# learn_to_solder.net
KiCad netlist of a schematic drawn in EAGLE
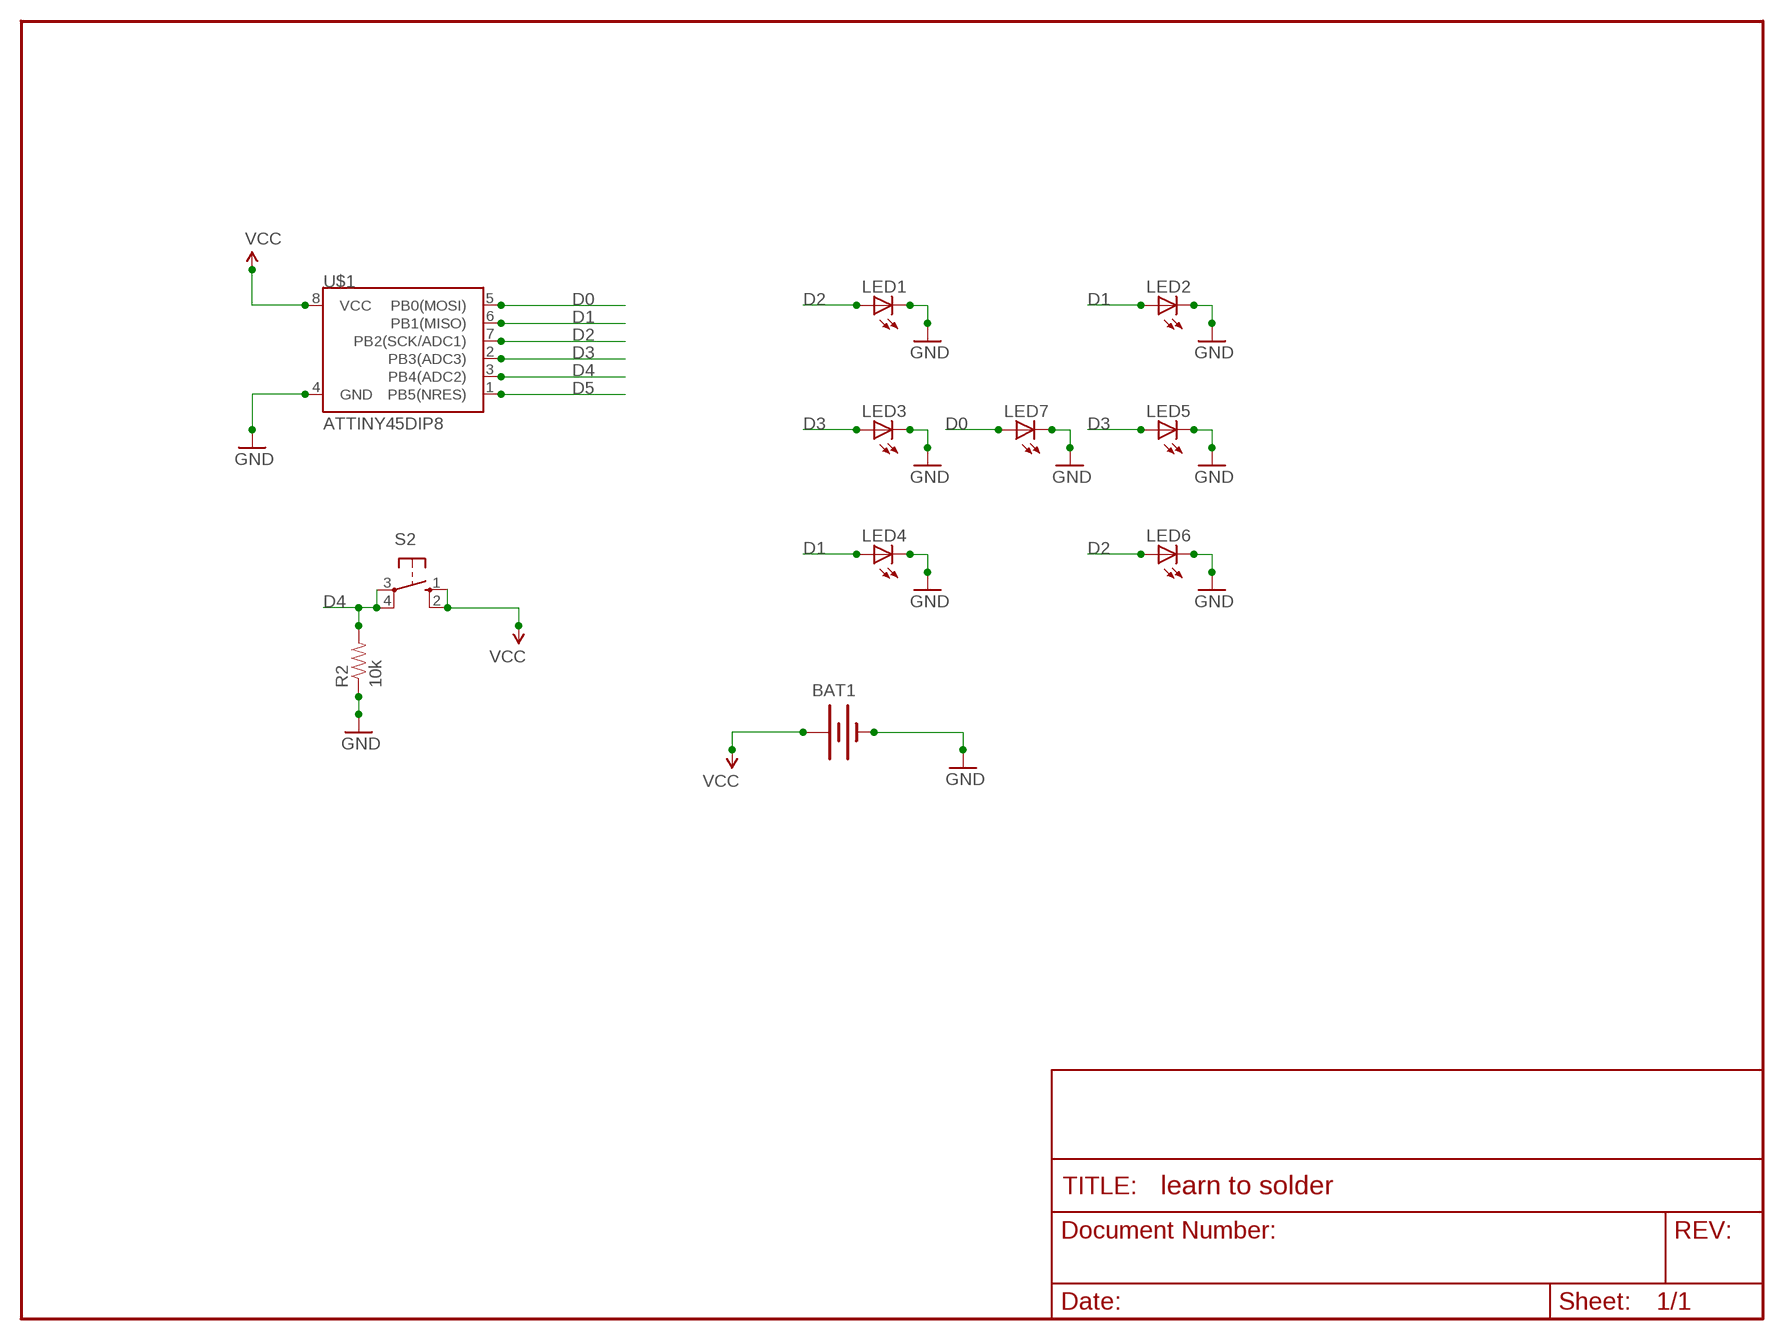
[diagram p0: schematic, sheet 1]

(export (version "E")
  (design (tool "Eeschema 10.0.6"))
  (components
    (comp (ref "BAT1")
      (value "BATTERY20PTH")
      (footprint "eagle-import:BATTCOM_20MM_PTH")
      (libsource (lib "eagle-import") (part "BATTERY20PTH"))
    )
    (comp (ref "LED1")
      (value "LED5MM")
      (footprint "eagle-import:LED5MM")
      (libsource (lib "eagle-import") (part "LED5MM"))
    )
    (comp (ref "LED2")
      (value "LED5MM")
      (footprint "eagle-import:LED5MM")
      (libsource (lib "eagle-import") (part "LED5MM"))
    )
    (comp (ref "LED3")
      (value "LED5MM")
      (footprint "eagle-import:LED5MM")
      (libsource (lib "eagle-import") (part "LED5MM"))
    )
    (comp (ref "LED4")
      (value "LED5MM")
      (footprint "eagle-import:LED5MM")
      (libsource (lib "eagle-import") (part "LED5MM"))
    )
    (comp (ref "LED5")
      (value "LED5MM")
      (footprint "eagle-import:LED5MM")
      (libsource (lib "eagle-import") (part "LED5MM"))
    )
    (comp (ref "LED6")
      (value "LED5MM")
      (footprint "eagle-import:LED5MM")
      (libsource (lib "eagle-import") (part "LED5MM"))
    )
    (comp (ref "LED7")
      (value "LED5MM")
      (footprint "eagle-import:LED5MM")
      (libsource (lib "eagle-import") (part "LED5MM"))
    )
    (comp (ref "R2")
      (value "10k")
      (footprint "eagle-import:AXIAL-0.3")
      (libsource (lib "eagle-import") (part "RESISTORAXIAL-0.3"))
    )
    (comp (ref "S2")
      (value "40-XX")
      (footprint "eagle-import:B3F-40XX")
      (fields (field (name "MF") "OMRON COMPONENTS USA") (field (name "MPN") "B3F-4000"))
      (libsource (lib "eagle-import") (part "40-XX"))
    )
    (comp (ref "U$1")
      (value "ATTINY45DIP8")
      (footprint "eagle-import:DIP08")
      (libsource (lib "eagle-import") (part "ATTINY45DIP8"))
    )
  )
  (nets
    (net (code "1") (name "/D0") (class "Default")
      (node (ref "LED7") (pin "A") (pinfunction "A_A") (pintype "passive"))
      (node (ref "U$1") (pin "5") (pinfunction "PB0(MOSI)_5") (pintype "bidirectional"))
    )
    (net (code "2") (name "/D1") (class "Default")
      (node (ref "LED2") (pin "A") (pinfunction "A_A") (pintype "passive"))
      (node (ref "LED4") (pin "A") (pinfunction "A_A") (pintype "passive"))
      (node (ref "U$1") (pin "6") (pinfunction "PB1(MISO)_6") (pintype "bidirectional"))
    )
    (net (code "3") (name "/D2") (class "Default")
      (node (ref "LED1") (pin "A") (pinfunction "A_A") (pintype "passive"))
      (node (ref "LED6") (pin "A") (pinfunction "A_A") (pintype "passive"))
      (node (ref "U$1") (pin "7") (pinfunction "PB2(SCK/ADC1)_7") (pintype "bidirectional"))
    )
    (net (code "4") (name "/D3") (class "Default")
      (node (ref "LED3") (pin "A") (pinfunction "A_A") (pintype "passive"))
      (node (ref "LED5") (pin "A") (pinfunction "A_A") (pintype "passive"))
      (node (ref "U$1") (pin "2") (pinfunction "PB3(ADC3)_2") (pintype "bidirectional"))
    )
    (net (code "5") (name "/D4") (class "Default")
      (node (ref "R2") (pin "P$2") (pinfunction "2_P$2") (pintype "passive"))
      (node (ref "S2") (pin "3") (pinfunction "P_3") (pintype "passive"))
      (node (ref "S2") (pin "4") (pinfunction "P1_4") (pintype "passive"))
      (node (ref "U$1") (pin "3") (pinfunction "PB4(ADC2)_3") (pintype "bidirectional"))
    )
    (net (code "6") (name "/D5") (class "Default")
      (node (ref "U$1") (pin "1") (pinfunction "PB5(NRES)_1") (pintype "bidirectional"))
    )
    (net (code "7") (name "GND") (class "Default")
      (node (ref "BAT1") (pin "2") (pinfunction "-_2") (pintype "power_in"))
      (node (ref "LED1") (pin "K") (pinfunction "C_K") (pintype "passive"))
      (node (ref "LED2") (pin "K") (pinfunction "C_K") (pintype "passive"))
      (node (ref "LED3") (pin "K") (pinfunction "C_K") (pintype "passive"))
      (node (ref "LED4") (pin "K") (pinfunction "C_K") (pintype "passive"))
      (node (ref "LED5") (pin "K") (pinfunction "C_K") (pintype "passive"))
      (node (ref "LED6") (pin "K") (pinfunction "C_K") (pintype "passive"))
      (node (ref "LED7") (pin "K") (pinfunction "C_K") (pintype "passive"))
      (node (ref "R2") (pin "P$1") (pinfunction "1_P$1") (pintype "passive"))
      (node (ref "U$1") (pin "4") (pinfunction "GND_4") (pintype "bidirectional"))
    )
    (net (code "8") (name "VCC") (class "Default")
      (node (ref "BAT1") (pin "1") (pinfunction "+_1") (pintype "power_in"))
      (node (ref "S2") (pin "1") (pinfunction "S_1") (pintype "passive"))
      (node (ref "S2") (pin "2") (pinfunction "S1_2") (pintype "passive"))
      (node (ref "U$1") (pin "8") (pinfunction "VCC_8") (pintype "bidirectional"))
    )
  )
)
